# DIOT_Backplane_Mezzaine.net
KiCad netlist of a schematic drawn in Altium Designer
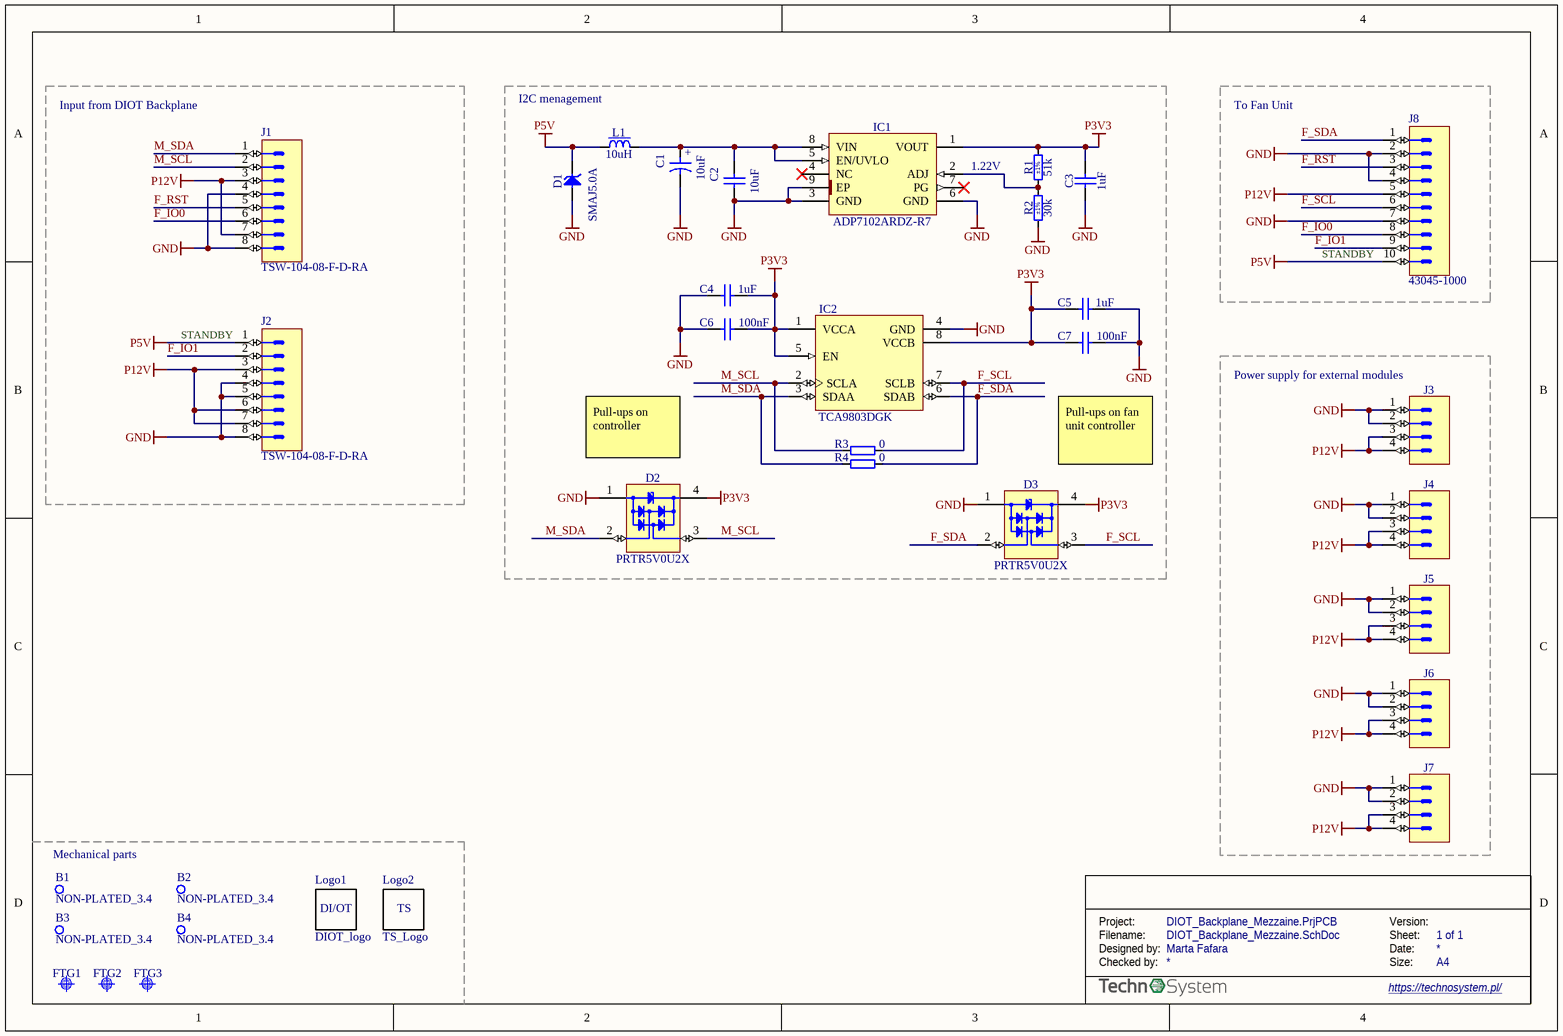
[diagram p0: DIOT_Backplane_Mezzaine.SchDoc]

(export (version "E")
  (design (tool "Eeschema 10.0.6"))
  (components
    (comp (ref "B1")
      (value "NON-PLATED_3.4")
      (footprint "MTG340")
      (description "Non Plated hole with diameter 3.4MM for screw M3")
      (libsource (lib "TechnoSystem Workspace") (part "NON-PLATED_3.4"))
    )
    (comp (ref "B2")
      (value "NON-PLATED_3.4")
      (footprint "MTG340")
      (description "Non Plated hole with diameter 3.4MM for screw M3")
      (libsource (lib "TechnoSystem Workspace") (part "NON-PLATED_3.4"))
    )
    (comp (ref "B3")
      (value "NON-PLATED_3.4")
      (footprint "MTG340")
      (description "Non Plated hole with diameter 3.4MM for screw M3")
      (libsource (lib "TechnoSystem Workspace") (part "NON-PLATED_3.4"))
    )
    (comp (ref "B4")
      (value "NON-PLATED_3.4")
      (footprint "MTG340")
      (description "Non Plated hole with diameter 3.4MM for screw M3")
      (libsource (lib "TechnoSystem Workspace") (part "NON-PLATED_3.4"))
    )
    (comp (ref "C1")
      (value "10uF")
      (footprint "CAPMP3216X180N")
      (description "Polarised capacitor")
      (fields
        (field (name "PART NUMBER") "CTE3216-18_10UF_16V_20%_AVX_TCJ")
        (field (name "VOLTAGE") "16V")
        (field (name "AUTHOR") "CERN DEM JLC")
      )
      (libsource (lib "Capacitors") (part "Capacitor - polarized"))
    )
    (comp (ref "C2")
      (value "10uF")
      (footprint "CAPC2012X135N")
      (description "Non-polarised capacitor")
      (fields
        (field (name "PART NUMBER") "CC0805_10UF_16V_10%_X5R")
        (field (name "VOLTAGE") "16V")
        (field (name "AUTHOR") "CERN DEM JLC")
      )
      (libsource (lib "Capacitors") (part "Capacitor - non polarized"))
    )
    (comp (ref "C3")
      (value "1uF")
      (footprint "CAPC1608X87N")
      (description "Non-polarised capacitor")
      (fields
        (field (name "PART NUMBER") "CC0603_1UF_25V_10%_X7R")
        (field (name "VOLTAGE") "25V")
        (field (name "AUTHOR") "CERN DEM JLC")
      )
      (libsource (lib "Capacitors") (part "Capacitor - non polarized"))
    )
    (comp (ref "C4")
      (value "1uF")
      (footprint "CAPC1608X87N")
      (description "Non-polarised capacitor")
      (fields
        (field (name "PART NUMBER") "CC0603_1UF_25V_10%_X7R")
        (field (name "VOLTAGE") "25V")
        (field (name "AUTHOR") "CERN DEM JLC")
      )
      (libsource (lib "Capacitors") (part "Capacitor - non polarized"))
    )
    (comp (ref "C5")
      (value "1uF")
      (footprint "CAPC1608X87N")
      (description "Non-polarised capacitor")
      (fields
        (field (name "PART NUMBER") "CC0603_1UF_25V_10%_X7R")
        (field (name "VOLTAGE") "25V")
        (field (name "AUTHOR") "CERN DEM JLC")
      )
      (libsource (lib "Capacitors") (part "Capacitor - non polarized"))
    )
    (comp (ref "C6")
      (value "100nF")
      (footprint "CAPC1005X55N")
      (description "Non-polarised capacitor")
      (fields
        (field (name "PART NUMBER") "CC0402_100NF_16V_10%_X7R")
        (field (name "VOLTAGE") "16V")
        (field (name "AUTHOR") "CERN DEM JLC")
      )
      (libsource (lib "Capacitors") (part "Capacitor - non polarized"))
    )
    (comp (ref "C7")
      (value "100nF")
      (footprint "CAPC1005X55N")
      (description "Non-polarised capacitor")
      (fields
        (field (name "PART NUMBER") "CC0402_100NF_16V_10%_X7R")
        (field (name "VOLTAGE") "16V")
        (field (name "AUTHOR") "CERN DEM JLC")
      )
      (libsource (lib "Capacitors") (part "Capacitor - non polarized"))
    )
    (comp (ref "D1")
      (value "SMAJ5.0A")
      (footprint "DIOM5226X262N")
      (description "Transient Voltage Suppressor Diode (Uni-Directional)")
      (fields
        (field (name "VOLTAGE") "5V")
        (field (name "POWER") "400W")
        (field (name "AUTHOR") "CERN DEM MR")
      )
      (libsource (lib "ICs And Semiconductors") (part "Diode TVS Uni-Directional"))
    )
    (comp (ref "D2")
      (value "PRTR5V0U2X")
      (footprint "SOT190P230X110-4N")
      (description "Ultra Low Capacitance Double Rail-to-Rail ESD Protection Diode")
      (fields
        (field (name "VOLTAGE") "5.5V")
        (field (name "MANUFACTURER") "NXP SEMICONDUCTORS")
        (field (name "AUTHOR") "CERN DEM JLC")
      )
      (libsource (lib "ICs And Semiconductors") (part "PRTR5V0U2X"))
    )
    (comp (ref "D3")
      (value "PRTR5V0U2X")
      (footprint "SOT190P230X110-4N")
      (description "Ultra Low Capacitance Double Rail-to-Rail ESD Protection Diode")
      (fields
        (field (name "VOLTAGE") "5.5V")
        (field (name "MANUFACTURER") "NXP SEMICONDUCTORS")
        (field (name "AUTHOR") "CERN DEM JLC")
      )
      (libsource (lib "ICs And Semiconductors") (part "PRTR5V0U2X"))
    )
    (comp (ref "FTG1")
      (value "Use only in PCB")
      (footprint "FIDUCIAL_TOP_C100-200")
      (description "Fiducial Target")
      (fields (field (name "PART NUMBER") "FIDUCIAL_TARGET_C100-200") (field (name "AUTHOR") "CERN DEM JLC"))
      (libsource (lib "Eletro-mechanical") (part "Fiducial Target"))
    )
    (comp (ref "FTG2")
      (value "Use only in PCB")
      (footprint "FIDUCIAL_TOP_C100-200")
      (description "Fiducial Target")
      (fields (field (name "PART NUMBER") "FIDUCIAL_TARGET_C100-200") (field (name "AUTHOR") "CERN DEM JLC"))
      (libsource (lib "Eletro-mechanical") (part "Fiducial Target"))
    )
    (comp (ref "FTG3")
      (value "Use only in PCB")
      (footprint "FIDUCIAL_TOP_C100-200")
      (description "Fiducial Target")
      (fields (field (name "PART NUMBER") "FIDUCIAL_TARGET_C100-200") (field (name "AUTHOR") "CERN DEM JLC"))
      (libsource (lib "Eletro-mechanical") (part "Fiducial Target"))
    )
    (comp (ref "IC1")
      (value "ADP7102ARDZ-R7")
      (footprint "SOIC127P600X175-9N-R241X309")
      (description "1.22V to 19V, 300mA, Low Noise, CMOS LDO Adjustable Linear Regulator")
      (fields (field (name "MANUFACTURER") "ANALOG DEVICES") (field (name "AUTHOR") "CERN DEM JLC"))
      (libsource (lib "ICs And Semiconductors") (part "ADP7102ARDZ-R7"))
    )
    (comp (ref "IC2")
      (value "TCA9803DGK")
      (footprint "SOP65P490X110-8N")
      (description "Level-Translating I2C Bus Buffer/Repeater")
      (fields (field (name "MANUFACTURER") "TEXAS INSTRUMENTS") (field (name "AUTHOR") "CERN DEM HF"))
      (libsource (lib "ICs And Semiconductors") (part "TCA9803"))
    )
    (comp (ref "J1")
      (value "TSW-104-08-F-D-RA")
      (footprint "TSW-104-08-F-D-RA")
      (libsource (lib "TechnoSystem Workspace") (part "8 pin male"))
    )
    (comp (ref "J2")
      (value "TSW-104-08-F-D-RA")
      (footprint "TSW-104-08-F-D-RA")
      (libsource (lib "TechnoSystem Workspace") (part "8 pin male"))
    )
    (comp (ref "J3")
      (value "Mini-Fit Jr.™")
      (footprint "MOLEX_39-30-0040")
      (description "Connector 4 Male")
      (fields
        (field (name "PART NUMBER") "MOLEX_39-30-0040")
        (field (name "MANUFACTURER") "MOLEX")
        (field (name "AUTHOR") "CERN DEM JLC")
      )
      (libsource (lib "Connectors") (part "Connector 4 Male"))
    )
    (comp (ref "J4")
      (value "Mini-Fit Jr.™")
      (footprint "MOLEX_39-30-0040")
      (description "Connector 4 Male")
      (fields
        (field (name "PART NUMBER") "MOLEX_39-30-0040")
        (field (name "MANUFACTURER") "MOLEX")
        (field (name "AUTHOR") "CERN DEM JLC")
      )
      (libsource (lib "Connectors") (part "Connector 4 Male"))
    )
    (comp (ref "J5")
      (value "Mini-Fit Jr.™")
      (footprint "MOLEX_39-30-0040")
      (description "Connector 4 Male")
      (fields
        (field (name "PART NUMBER") "MOLEX_39-30-0040")
        (field (name "MANUFACTURER") "MOLEX")
        (field (name "AUTHOR") "CERN DEM JLC")
      )
      (libsource (lib "Connectors") (part "Connector 4 Male"))
    )
    (comp (ref "J6")
      (value "Mini-Fit Jr.™")
      (footprint "MOLEX_39-30-0040")
      (description "Connector 4 Male")
      (fields
        (field (name "PART NUMBER") "MOLEX_39-30-0040")
        (field (name "MANUFACTURER") "MOLEX")
        (field (name "AUTHOR") "CERN DEM JLC")
      )
      (libsource (lib "Connectors") (part "Connector 4 Male"))
    )
    (comp (ref "J7")
      (value "Mini-Fit Jr.™")
      (footprint "MOLEX_39-30-0040")
      (description "Connector 4 Male")
      (fields
        (field (name "PART NUMBER") "MOLEX_39-30-0040")
        (field (name "MANUFACTURER") "MOLEX")
        (field (name "AUTHOR") "CERN DEM JLC")
      )
      (libsource (lib "Connectors") (part "Connector 4 Male"))
    )
    (comp (ref "J8")
      (value "43045-1000")
      (footprint "43045-1000")
      (description "Rectangular Power Connector, 10 Contact(s), Male, Solder Terminal, Receptacle")
      (libsource (lib "TechnoSystem Workspace") (part "10 pin male"))
    )
    (comp (ref "L1")
      (value "10uH")
      (footprint "IND_MURATA_LQW32FT_0H")
      (description "Inductor With Core")
      (fields
        (field (name "PART NUMBER") "IND1210_10UH_20%_MURATA_LQW32FT100M0H")
        (field (name "POWER") "500mA")
        (field (name "AUTHOR") "CERN DEM BC")
      )
      (libsource (lib "Inductors & Transformers") (part "Inductor With Magnetic core"))
    )
    (comp (ref "Logo1")
      (value "DIOT_logo")
      (footprint "DIOT_logo")
      (description "Logo of DI/OT system")
      (libsource (lib "TechnoSystem Workspace") (part "DIOT_logo"))
    )
    (comp (ref "Logo2")
      (value "TS_Logo")
      (footprint "TS_Logo")
      (description "Logo of TechnoSystem")
      (libsource (lib "TechnoSystem Workspace") (part "TS_Logo"))
    )
    (comp (ref "R1")
      (value "51k")
      (footprint "RESC1005X40N")
      (description "Resistor - 1%")
      (fields
        (field (name "TOLERANCE") "±1%")
        (field (name "PART NUMBER") "R0402_51K_1%_0.0625W_100PPM")
        (field (name "POWER") "0.0625W")
        (field (name "AUTHOR") "CERN DEM JLC")
      )
      (libsource (lib "Resistors") (part "Resistor - 1%"))
    )
    (comp (ref "R2")
      (value "30k")
      (footprint "RESC1005X40N")
      (description "Resistor - 1%")
      (fields
        (field (name "TOLERANCE") "±1%")
        (field (name "PART NUMBER") "R0402_30K_1%_0.0625W_100PPM")
        (field (name "POWER") "0.0625W")
        (field (name "AUTHOR") "CERN DEM JLC")
      )
      (libsource (lib "Resistors") (part "Resistor - 1%"))
    )
    (comp (ref "R3")
      (value "0")
      (footprint "RESC1608X55N")
      (description "Resistor")
      (fields
        (field (name "PART NUMBER") "R0603_0R_JUMPER")
        (field (name "MANUFACTURER") "GENERIC")
        (field (name "AUTHOR") "CERN DEM JLC")
      )
      (libsource (lib "Resistors") (part "Resistor"))
    )
    (comp (ref "R4")
      (value "0")
      (footprint "RESC1608X55N")
      (description "Resistor")
      (fields
        (field (name "PART NUMBER") "R0603_0R_JUMPER")
        (field (name "MANUFACTURER") "GENERIC")
        (field (name "AUTHOR") "CERN DEM JLC")
      )
      (libsource (lib "Resistors") (part "Resistor"))
    )
  )
  (nets
    (net (code "1") (name "/F_IO0") (class "Default")
      (node (ref "J1") (pin "6") (pinfunction "6_6") (pintype "bidirectional"))
      (node (ref "J8") (pin "8") (pinfunction "8_8") (pintype "bidirectional"))
    )
    (net (code "2") (name "/F_IO1") (class "Default")
      (node (ref "J2") (pin "2") (pinfunction "2_2") (pintype "bidirectional"))
      (node (ref "J8") (pin "9") (pinfunction "9_9") (pintype "bidirectional"))
    )
    (net (code "3") (name "/F_RST") (class "Default")
      (node (ref "J1") (pin "5") (pinfunction "5_5") (pintype "bidirectional"))
      (node (ref "J8") (pin "3") (pinfunction "3_3") (pintype "bidirectional"))
    )
    (net (code "4") (name "/F_SCL") (class "Default")
      (node (ref "D3") (pin "3") (pinfunction "I/O2_3") (pintype "bidirectional"))
      (node (ref "IC2") (pin "7") (pinfunction "SCLB_7") (pintype "bidirectional"))
      (node (ref "J8") (pin "6") (pinfunction "6_6") (pintype "bidirectional"))
      (node (ref "R3") (pin "2") (pinfunction "2_2") (pintype "passive"))
    )
    (net (code "5") (name "/F_SDA") (class "Default")
      (node (ref "D3") (pin "2") (pinfunction "I/O1_2") (pintype "bidirectional"))
      (node (ref "IC2") (pin "6") (pinfunction "SDAB_6") (pintype "bidirectional"))
      (node (ref "J8") (pin "1") (pinfunction "1_1") (pintype "bidirectional"))
      (node (ref "R4") (pin "2") (pinfunction "2_2") (pintype "passive"))
    )
    (net (code "6") (name "/M_SCL") (class "Default")
      (node (ref "D2") (pin "3") (pinfunction "I/O2_3") (pintype "bidirectional"))
      (node (ref "IC2") (pin "2") (pinfunction "SCLA_2") (pintype "bidirectional"))
      (node (ref "J1") (pin "2") (pinfunction "2_2") (pintype "bidirectional"))
      (node (ref "R3") (pin "1") (pinfunction "1_1") (pintype "passive"))
    )
    (net (code "7") (name "/M_SDA") (class "Default")
      (node (ref "D2") (pin "2") (pinfunction "I/O1_2") (pintype "bidirectional"))
      (node (ref "IC2") (pin "3") (pinfunction "SDAA_3") (pintype "bidirectional"))
      (node (ref "J1") (pin "1") (pinfunction "1_1") (pintype "bidirectional"))
      (node (ref "R4") (pin "1") (pinfunction "1_1") (pintype "passive"))
    )
    (net (code "8") (name "GND") (class "Default")
      (node (ref "C1") (pin "2") (pinfunction "2_2") (pintype "passive"))
      (node (ref "C2") (pin "2") (pinfunction "2_2") (pintype "passive"))
      (node (ref "C3") (pin "1") (pinfunction "1_1") (pintype "passive"))
      (node (ref "C4") (pin "1") (pinfunction "1_1") (pintype "passive"))
      (node (ref "C5") (pin "2") (pinfunction "2_2") (pintype "passive"))
      (node (ref "C6") (pin "1") (pinfunction "1_1") (pintype "passive"))
      (node (ref "C7") (pin "2") (pinfunction "2_2") (pintype "passive"))
      (node (ref "D1") (pin "2") (pinfunction "A_2") (pintype "passive"))
      (node (ref "D2") (pin "1") (pinfunction "GND_1") (pintype "power_in"))
      (node (ref "D3") (pin "1") (pinfunction "GND_1") (pintype "power_in"))
      (node (ref "IC1") (pin "3") (pinfunction "GND_3") (pintype "power_in"))
      (node (ref "IC1") (pin "6") (pinfunction "GND_6") (pintype "power_in"))
      (node (ref "IC1") (pin "9") (pinfunction "EP_9") (pintype "power_in"))
      (node (ref "IC2") (pin "4") (pinfunction "GND_4") (pintype "power_in"))
      (node (ref "J1") (pin "4") (pinfunction "4_4") (pintype "bidirectional"))
      (node (ref "J1") (pin "8") (pinfunction "8_8") (pintype "bidirectional"))
      (node (ref "J2") (pin "4") (pinfunction "4_4") (pintype "bidirectional"))
      (node (ref "J2") (pin "5") (pinfunction "5_5") (pintype "bidirectional"))
      (node (ref "J2") (pin "8") (pinfunction "8_8") (pintype "bidirectional"))
      (node (ref "J3") (pin "1") (pinfunction "1_1") (pintype "bidirectional"))
      (node (ref "J3") (pin "2") (pinfunction "2_2") (pintype "bidirectional"))
      (node (ref "J4") (pin "1") (pinfunction "1_1") (pintype "bidirectional"))
      (node (ref "J4") (pin "2") (pinfunction "2_2") (pintype "bidirectional"))
      (node (ref "J5") (pin "1") (pinfunction "1_1") (pintype "bidirectional"))
      (node (ref "J5") (pin "2") (pinfunction "2_2") (pintype "bidirectional"))
      (node (ref "J6") (pin "1") (pinfunction "1_1") (pintype "bidirectional"))
      (node (ref "J6") (pin "2") (pinfunction "2_2") (pintype "bidirectional"))
      (node (ref "J7") (pin "1") (pinfunction "1_1") (pintype "bidirectional"))
      (node (ref "J7") (pin "2") (pinfunction "2_2") (pintype "bidirectional"))
      (node (ref "J8") (pin "2") (pinfunction "2_2") (pintype "bidirectional"))
      (node (ref "J8") (pin "4") (pinfunction "4_4") (pintype "bidirectional"))
      (node (ref "J8") (pin "7") (pinfunction "7_7") (pintype "bidirectional"))
      (node (ref "R2") (pin "1") (pinfunction "1_1") (pintype "passive"))
    )
    (net (code "9") (name "Net-(IC1-ADJ)") (class "Default")
      (node (ref "IC1") (pin "2") (pinfunction "ADJ_2") (pintype "input"))
      (node (ref "R1") (pin "1") (pinfunction "1_1") (pintype "passive"))
      (node (ref "R2") (pin "2") (pinfunction "2_2") (pintype "passive"))
    )
    (net (code "10") (name "Net-(IC1-EN{slash}UVLO)") (class "Default")
      (node (ref "C1") (pin "1") (pinfunction "1_1") (pintype "passive"))
      (node (ref "C2") (pin "1") (pinfunction "1_1") (pintype "passive"))
      (node (ref "IC1") (pin "5") (pinfunction "EN/UVLO_5") (pintype "input"))
      (node (ref "IC1") (pin "8") (pinfunction "VIN_8") (pintype "input"))
      (node (ref "L1") (pin "2") (pinfunction "2_2") (pintype "passive"))
    )
    (net (code "11") (name "P3V3") (class "Default")
      (node (ref "C3") (pin "2") (pinfunction "2_2") (pintype "passive"))
      (node (ref "C4") (pin "2") (pinfunction "2_2") (pintype "passive"))
      (node (ref "C5") (pin "1") (pinfunction "1_1") (pintype "passive"))
      (node (ref "C6") (pin "2") (pinfunction "2_2") (pintype "passive"))
      (node (ref "C7") (pin "1") (pinfunction "1_1") (pintype "passive"))
      (node (ref "D2") (pin "4") (pinfunction "VCC_4") (pintype "power_in"))
      (node (ref "D3") (pin "4") (pinfunction "VCC_4") (pintype "power_in"))
      (node (ref "IC1") (pin "1") (pinfunction "VOUT_1") (pintype "power_in"))
      (node (ref "IC2") (pin "1") (pinfunction "VCCA_1") (pintype "power_in"))
      (node (ref "IC2") (pin "5") (pinfunction "EN_5") (pintype "input"))
      (node (ref "IC2") (pin "8") (pinfunction "VCCB_8") (pintype "power_in"))
      (node (ref "R1") (pin "2") (pinfunction "2_2") (pintype "passive"))
    )
    (net (code "12") (name "P5V") (class "Default")
      (node (ref "D1") (pin "1") (pinfunction "C_1") (pintype "passive"))
      (node (ref "J2") (pin "1") (pinfunction "1_1") (pintype "bidirectional"))
      (node (ref "J8") (pin "10") (pinfunction "10_10") (pintype "bidirectional"))
      (node (ref "L1") (pin "1") (pinfunction "1_1") (pintype "passive"))
    )
    (net (code "13") (name "P12V") (class "Default")
      (node (ref "J1") (pin "3") (pinfunction "3_3") (pintype "bidirectional"))
      (node (ref "J1") (pin "7") (pinfunction "7_7") (pintype "bidirectional"))
      (node (ref "J2") (pin "3") (pinfunction "3_3") (pintype "bidirectional"))
      (node (ref "J2") (pin "6") (pinfunction "6_6") (pintype "bidirectional"))
      (node (ref "J2") (pin "7") (pinfunction "7_7") (pintype "bidirectional"))
      (node (ref "J3") (pin "3") (pinfunction "3_3") (pintype "bidirectional"))
      (node (ref "J3") (pin "4") (pinfunction "4_4") (pintype "bidirectional"))
      (node (ref "J4") (pin "3") (pinfunction "3_3") (pintype "bidirectional"))
      (node (ref "J4") (pin "4") (pinfunction "4_4") (pintype "bidirectional"))
      (node (ref "J5") (pin "3") (pinfunction "3_3") (pintype "bidirectional"))
      (node (ref "J5") (pin "4") (pinfunction "4_4") (pintype "bidirectional"))
      (node (ref "J6") (pin "3") (pinfunction "3_3") (pintype "bidirectional"))
      (node (ref "J6") (pin "4") (pinfunction "4_4") (pintype "bidirectional"))
      (node (ref "J7") (pin "3") (pinfunction "3_3") (pintype "bidirectional"))
      (node (ref "J7") (pin "4") (pinfunction "4_4") (pintype "bidirectional"))
      (node (ref "J8") (pin "5") (pinfunction "5_5") (pintype "bidirectional"))
    )
    (net (code "14") (name "unconnected-(B1-Pad1)") (class "Default")
      (node (ref "B1") (pin "1") (pinfunction "1_1") (pintype "bidirectional"))
    )
    (net (code "15") (name "unconnected-(B2-Pad1)") (class "Default")
      (node (ref "B2") (pin "1") (pinfunction "1_1") (pintype "bidirectional"))
    )
    (net (code "16") (name "unconnected-(B3-Pad1)") (class "Default")
      (node (ref "B3") (pin "1") (pinfunction "1_1") (pintype "bidirectional"))
    )
    (net (code "17") (name "unconnected-(B4-Pad1)") (class "Default")
      (node (ref "B4") (pin "1") (pinfunction "1_1") (pintype "bidirectional"))
    )
    (net (code "18") (name "unconnected-(IC1-NC-Pad4)") (class "Default")
      (node (ref "IC1") (pin "4") (pinfunction "NC_4") (pintype "passive+no_connect"))
    )
    (net (code "19") (name "unconnected-(IC1-PG-Pad7)") (class "Default")
      (node (ref "IC1") (pin "7") (pinfunction "PG_7") (pintype "output+no_connect"))
    )
  )
)
